# water_controller_1.net
KiCad netlist of a schematic drawn in Altium Designer
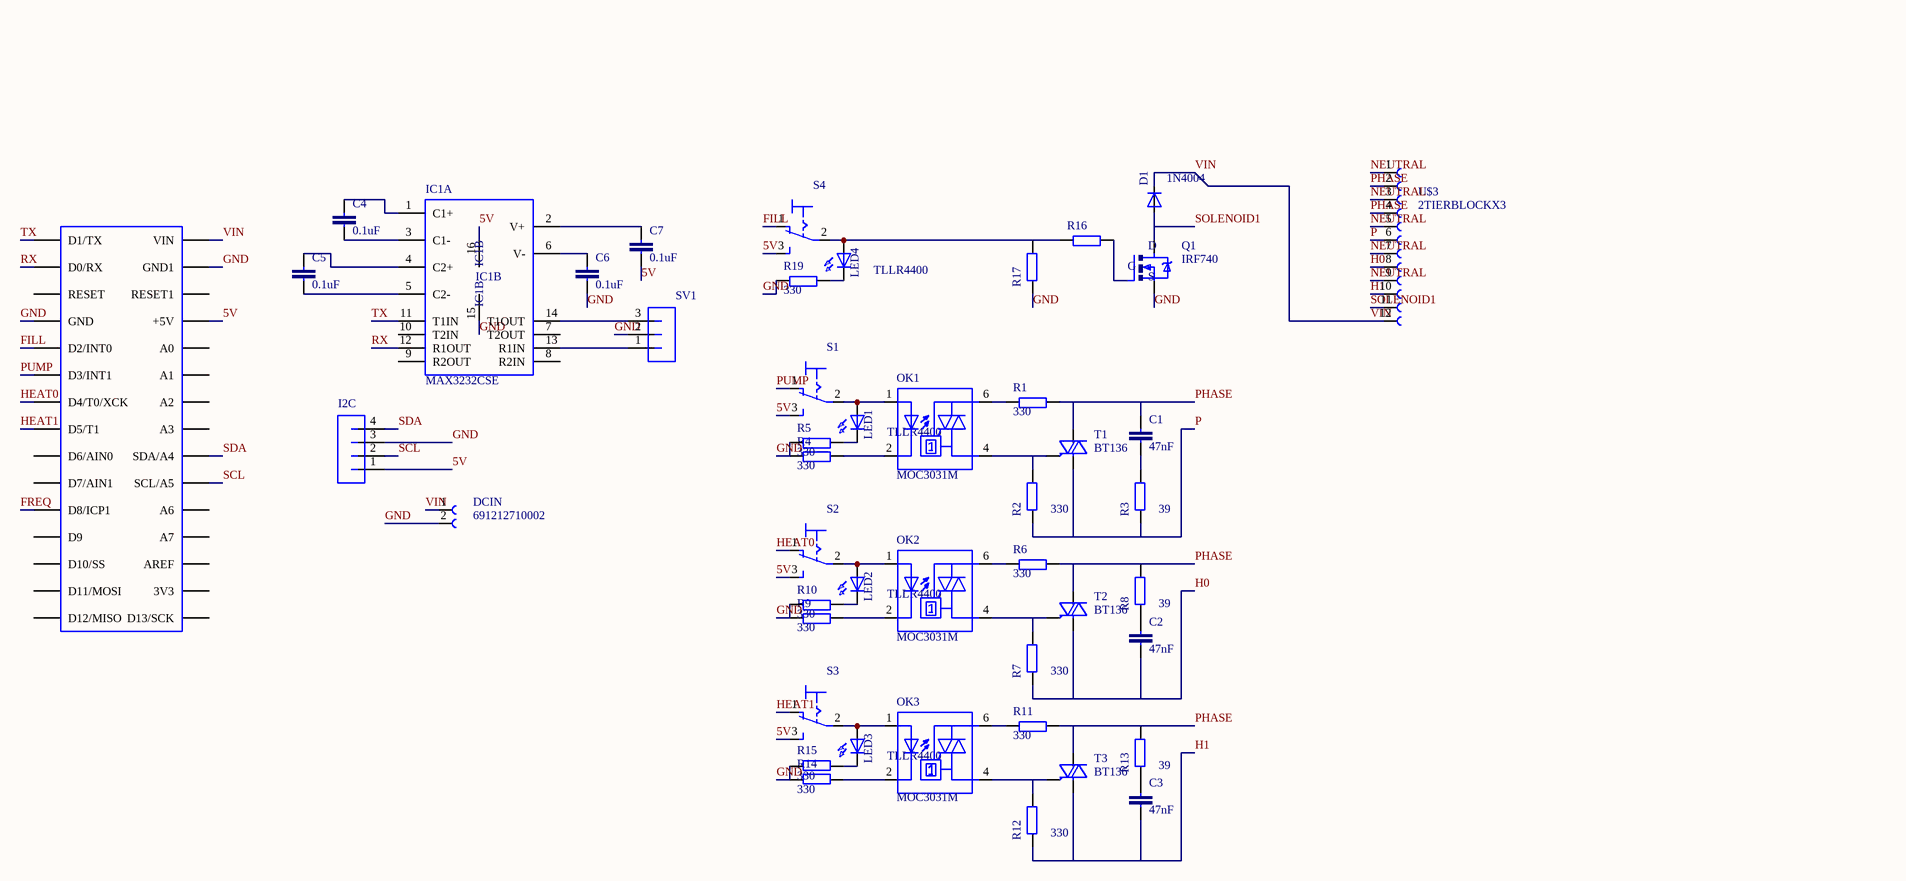
[diagram p0: water_controller_1.SchDoc]

(export (version "E")
  (design (tool "Eeschema 10.0.6"))
  (components
    (comp (ref "C1")
      (value "47nF")
      (footprint "C150-064X183")
      (libsource (lib "rcl") (part "C-EU150-064X183"))
    )
    (comp (ref "C2")
      (value "47nF")
      (footprint "C150-064X183")
      (libsource (lib "rcl") (part "C-EU150-064X183"))
    )
    (comp (ref "C3")
      (value "47nF")
      (footprint "C150-064X183")
      (libsource (lib "rcl") (part "C-EU150-064X183"))
    )
    (comp (ref "C4") (value "0.1uF") (footprint "C1210") (libsource (lib "rcl") (part "C-EUC1210")))
    (comp (ref "C5") (value "0.1uF") (footprint "C1210") (libsource (lib "rcl") (part "C-EUC1210")))
    (comp (ref "C6") (value "0.1uF") (footprint "C1210") (libsource (lib "rcl") (part "C-EUC1210")))
    (comp (ref "C7") (value "0.1uF") (footprint "C1210") (libsource (lib "rcl") (part "C-EUC1210")))
    (comp (ref "D1") (value "1N4004") (footprint "DO41-10") (libsource (lib "diode") (part "1N4004")))
    (comp (ref "DCIN")
      (value "691212710002")
      (footprint "691212710002")
      (libsource (lib "ZugbuegelsystemWR-TBL") (part "691212710002"))
    )
    (comp (ref "I2C") (value "~") (footprint "MA04-1") (libsource (lib "con-lstb") (part "MA04-1")))
    (comp (ref "IC1") (value "MAX3232CSE") (footprint "SO16") (libsource (lib "") (part "MAX3232CSE_1")))
    (comp (ref "LED1") (value "TLLR4400") (footprint "LED3MM") (libsource (lib "led") (part "TLLR4400")))
    (comp (ref "LED2") (value "TLLR4400") (footprint "LED3MM") (libsource (lib "led") (part "TLLR4400")))
    (comp (ref "LED3") (value "TLLR4400") (footprint "LED3MM") (libsource (lib "") (part "TLLR4400_1")))
    (comp (ref "LED4") (value "TLLR4400") (footprint "LED3MM") (libsource (lib "led") (part "TLLR4400")))
    (comp (ref "OK1")
      (value "MOC3031M")
      (footprint "DIL06")
      (libsource (lib "optocoupler") (part "MOC3031M"))
    )
    (comp (ref "OK2")
      (value "MOC3031M")
      (footprint "DIL06")
      (libsource (lib "optocoupler") (part "MOC3031M"))
    )
    (comp (ref "OK3")
      (value "MOC3031M")
      (footprint "DIL06")
      (libsource (lib "optocoupler") (part "MOC3031M"))
    )
    (comp (ref "Q1")
      (value "IRF740")
      (footprint "TO220BV")
      (libsource (lib "transistor-power") (part "IRF740"))
    )
    (comp (ref "R1") (value "330") (footprint "M1206") (libsource (lib "rcl") (part "R-EU_M1206")))
    (comp (ref "R2") (value "330") (footprint "M1206") (libsource (lib "") (part "R-EU_M1206_1")))
    (comp (ref "R3") (value "39") (footprint "M1206") (libsource (lib "") (part "R-EU_M1206_1")))
    (comp (ref "R4") (value "330") (footprint "R1206") (libsource (lib "rcl") (part "R-EU_R1206")))
    (comp (ref "R5") (value "330") (footprint "R1206") (libsource (lib "rcl") (part "R-EU_R1206")))
    (comp (ref "R6") (value "330") (footprint "M1206") (libsource (lib "rcl") (part "R-EU_M1206")))
    (comp (ref "R7") (value "330") (footprint "M1206") (libsource (lib "") (part "R-EU_M1206_1")))
    (comp (ref "R8") (value "39") (footprint "M1206") (libsource (lib "") (part "R-EU_M1206_1")))
    (comp (ref "R9") (value "330") (footprint "R1206") (libsource (lib "rcl") (part "R-EU_R1206")))
    (comp (ref "R10") (value "330") (footprint "R1206") (libsource (lib "rcl") (part "R-EU_R1206")))
    (comp (ref "R11") (value "330") (footprint "M1206") (libsource (lib "rcl") (part "R-EU_M1206")))
    (comp (ref "R12") (value "330") (footprint "M1206") (libsource (lib "") (part "R-EU_M1206_1")))
    (comp (ref "R13") (value "39") (footprint "M1206") (libsource (lib "") (part "R-EU_M1206_1")))
    (comp (ref "R14") (value "330") (footprint "R1206") (libsource (lib "") (part "R-EU_R1206_1")))
    (comp (ref "R15") (value "330") (footprint "R1206") (libsource (lib "") (part "R-EU_R1206_1")))
    (comp (ref "R16") (value "~") (footprint "M1206") (libsource (lib "rcl") (part "R-EU_M1206")))
    (comp (ref "R17") (value "~") (footprint "M1206") (libsource (lib "") (part "R-EU_M1206_1")))
    (comp (ref "R19") (value "330") (footprint "R1206") (libsource (lib "rcl") (part "R-EU_R1206")))
    (comp (ref "S1") (value "~") (footprint "M9040P") (libsource (lib "switch") (part "M9040P")))
    (comp (ref "S2") (value "~") (footprint "M9040P") (libsource (lib "switch") (part "M9040P")))
    (comp (ref "S3") (value "~") (footprint "M9040P") (libsource (lib "switch") (part "M9040P")))
    (comp (ref "S4") (value "~") (footprint "M9040P") (libsource (lib "switch") (part "M9040P")))
    (comp (ref "SV1") (value "~") (footprint "MA03-1") (libsource (lib "con-lstb") (part "MA03-1")))
    (comp (ref "T1") (value "BT136") (footprint "TO220AVH") (libsource (lib "jet-lib") (part "BT136")))
    (comp (ref "T2") (value "BT136") (footprint "TO220AVH") (libsource (lib "jet-lib") (part "BT136")))
    (comp (ref "T3") (value "BT136") (footprint "TO220AVH") (libsource (lib "jet-lib") (part "BT136")))
    (comp (ref "U$1") (value "~") (footprint "PDIP-32") (libsource (lib "jet-lib") (part "ARDUINONANO")))
    (comp (ref "U$3")
      (value "2TIERBLOCKX3")
      (footprint "2TIERX3")
      (libsource (lib "jet-lib") (part "2TIERBLOCKX3"))
    )
  )
  (nets
    (net (code "1") (name "/5V") (class "Default")
      (node (ref "C7") (pin "2") (pinfunction "2_2") (pintype "passive"))
      (node (ref "I2C") (pin "1") (pinfunction "1_1") (pintype "passive"))
      (node (ref "IC1") (pin "16") (pinfunction "VCC_16") (pintype "passive"))
      (node (ref "S1") (pin "3") (pinfunction "S_3") (pintype "passive"))
      (node (ref "S2") (pin "3") (pinfunction "S_3") (pintype "passive"))
      (node (ref "S3") (pin "3") (pinfunction "S_3") (pintype "passive"))
      (node (ref "S4") (pin "3") (pinfunction "S_3") (pintype "passive"))
      (node (ref "U$1") (pin "+5V") (pinfunction "+5V_+5V") (pintype "passive"))
    )
    (net (code "2") (name "/FILL") (class "Default")
      (node (ref "S4") (pin "1") (pinfunction "O_1") (pintype "passive"))
      (node (ref "U$1") (pin "D2") (pinfunction "D2/INT0_D2") (pintype "passive"))
    )
    (net (code "3") (name "/FREQ") (class "Default")
      (node (ref "U$1") (pin "D8") (pinfunction "D8/ICP1_D8") (pintype "passive"))
    )
    (net (code "4") (name "/GND") (class "Default")
      (node (ref "C6") (pin "2") (pinfunction "2_2") (pintype "passive"))
      (node (ref "DCIN") (pin "2") (pinfunction "2_2") (pintype "passive"))
      (node (ref "I2C") (pin "3") (pinfunction "3_3") (pintype "passive"))
      (node (ref "IC1") (pin "15") (pinfunction "GND_15") (pintype "passive"))
      (node (ref "Q1") (pin "S") (pinfunction "S_S") (pintype "passive"))
      (node (ref "R10") (pin "1") (pinfunction "1_1") (pintype "passive"))
      (node (ref "R14") (pin "1") (pinfunction "1_1") (pintype "passive"))
      (node (ref "R15") (pin "1") (pinfunction "1_1") (pintype "passive"))
      (node (ref "R17") (pin "1") (pinfunction "1_1") (pintype "passive"))
      (node (ref "R19") (pin "1") (pinfunction "1_1") (pintype "passive"))
      (node (ref "R4") (pin "1") (pinfunction "1_1") (pintype "passive"))
      (node (ref "R5") (pin "1") (pinfunction "1_1") (pintype "passive"))
      (node (ref "R9") (pin "1") (pinfunction "1_1") (pintype "passive"))
      (node (ref "SV1") (pin "2") (pinfunction "2_2") (pintype "passive"))
      (node (ref "U$1") (pin "GND") (pinfunction "GND_GND") (pintype "passive"))
      (node (ref "U$1") (pin "GND1") (pinfunction "GND1_GND1") (pintype "passive"))
    )
    (net (code "5") (name "/H0") (class "Default")
      (node (ref "C2") (pin "2") (pinfunction "2_2") (pintype "passive"))
      (node (ref "R7") (pin "1") (pinfunction "1_1") (pintype "passive"))
      (node (ref "T2") (pin "1") (pinfunction "T1_1") (pintype "passive"))
      (node (ref "U$3") (pin "8") (pinfunction "8_8") (pintype "passive"))
    )
    (net (code "6") (name "/H1") (class "Default")
      (node (ref "C3") (pin "2") (pinfunction "2_2") (pintype "passive"))
      (node (ref "R12") (pin "1") (pinfunction "1_1") (pintype "passive"))
      (node (ref "T3") (pin "1") (pinfunction "T1_1") (pintype "passive"))
      (node (ref "U$3") (pin "10") (pinfunction "10_10") (pintype "passive"))
    )
    (net (code "7") (name "/HEAT0") (class "Default")
      (node (ref "S2") (pin "1") (pinfunction "O_1") (pintype "passive"))
      (node (ref "U$1") (pin "D4") (pinfunction "D4/T0/XCK_D4") (pintype "passive"))
    )
    (net (code "8") (name "/HEAT1") (class "Default")
      (node (ref "S3") (pin "1") (pinfunction "O_1") (pintype "passive"))
      (node (ref "U$1") (pin "D5") (pinfunction "D5/T1_D5") (pintype "passive"))
    )
    (net (code "9") (name "/NEUTRAL") (class "Default")
      (node (ref "U$3") (pin "1") (pinfunction "1_1") (pintype "passive"))
      (node (ref "U$3") (pin "3") (pinfunction "3_3") (pintype "passive"))
      (node (ref "U$3") (pin "5") (pinfunction "5_5") (pintype "passive"))
      (node (ref "U$3") (pin "7") (pinfunction "7_7") (pintype "passive"))
      (node (ref "U$3") (pin "9") (pinfunction "9_9") (pintype "passive"))
    )
    (net (code "10") (name "/P") (class "Default")
      (node (ref "R2") (pin "1") (pinfunction "1_1") (pintype "passive"))
      (node (ref "R3") (pin "1") (pinfunction "1_1") (pintype "passive"))
      (node (ref "T1") (pin "1") (pinfunction "T1_1") (pintype "passive"))
      (node (ref "U$3") (pin "6") (pinfunction "6_6") (pintype "passive"))
    )
    (net (code "11") (name "/PHASE") (class "Default")
      (node (ref "C1") (pin "1") (pinfunction "1_1") (pintype "passive"))
      (node (ref "R1") (pin "2") (pinfunction "2_2") (pintype "passive"))
      (node (ref "R11") (pin "2") (pinfunction "2_2") (pintype "passive"))
      (node (ref "R13") (pin "2") (pinfunction "2_2") (pintype "passive"))
      (node (ref "R6") (pin "2") (pinfunction "2_2") (pintype "passive"))
      (node (ref "R8") (pin "2") (pinfunction "2_2") (pintype "passive"))
      (node (ref "T1") (pin "2") (pinfunction "T2_2") (pintype "passive"))
      (node (ref "T2") (pin "2") (pinfunction "T2_2") (pintype "passive"))
      (node (ref "T3") (pin "2") (pinfunction "T2_2") (pintype "passive"))
      (node (ref "U$3") (pin "2") (pinfunction "2_2") (pintype "passive"))
      (node (ref "U$3") (pin "4") (pinfunction "4_4") (pintype "passive"))
    )
    (net (code "12") (name "/PUMP") (class "Default")
      (node (ref "S1") (pin "1") (pinfunction "O_1") (pintype "passive"))
      (node (ref "U$1") (pin "D3") (pinfunction "D3/INT1_D3") (pintype "passive"))
    )
    (net (code "13") (name "/RX") (class "Default")
      (node (ref "IC1") (pin "12") (pinfunction "R1OUT_12") (pintype "passive"))
      (node (ref "U$1") (pin "D0/RX") (pinfunction "D0/RX_D0/RX") (pintype "passive"))
    )
    (net (code "14") (name "/SCL") (class "Default")
      (node (ref "I2C") (pin "2") (pinfunction "2_2") (pintype "passive"))
      (node (ref "U$1") (pin "A5") (pinfunction "SCL/A5_A5") (pintype "passive"))
    )
    (net (code "15") (name "/SDA") (class "Default")
      (node (ref "I2C") (pin "4") (pinfunction "4_4") (pintype "passive"))
      (node (ref "U$1") (pin "A4") (pinfunction "SDA/A4_A4") (pintype "passive"))
    )
    (net (code "16") (name "/SOLENOID1") (class "Default")
      (node (ref "D1") (pin "A") (pinfunction "A_A") (pintype "passive"))
      (node (ref "Q1") (pin "D") (pinfunction "D_D") (pintype "passive"))
      (node (ref "U$3") (pin "11") (pinfunction "11_11") (pintype "passive"))
    )
    (net (code "17") (name "/TX") (class "Default")
      (node (ref "IC1") (pin "11") (pinfunction "T1IN_11") (pintype "passive"))
      (node (ref "U$1") (pin "D1/TX") (pinfunction "D1/TX_D1/TX") (pintype "passive"))
    )
    (net (code "18") (name "/VIN") (class "Default")
      (node (ref "D1") (pin "C") (pinfunction "C_C") (pintype "passive"))
      (node (ref "DCIN") (pin "1") (pinfunction "1_1") (pintype "passive"))
      (node (ref "U$1") (pin "VIN") (pinfunction "VIN_VIN") (pintype "passive"))
      (node (ref "U$3") (pin "12") (pinfunction "12_12") (pintype "passive"))
    )
    (net (code "19") (name "Net-(C1-Pad2)") (class "Default")
      (node (ref "C1") (pin "2") (pinfunction "2_2") (pintype "passive"))
      (node (ref "R3") (pin "2") (pinfunction "2_2") (pintype "passive"))
    )
    (net (code "20") (name "Net-(C2-Pad1)") (class "Default")
      (node (ref "C2") (pin "1") (pinfunction "1_1") (pintype "passive"))
      (node (ref "R8") (pin "1") (pinfunction "1_1") (pintype "passive"))
    )
    (net (code "21") (name "Net-(C3-Pad1)") (class "Default")
      (node (ref "C3") (pin "1") (pinfunction "1_1") (pintype "passive"))
      (node (ref "R13") (pin "1") (pinfunction "1_1") (pintype "passive"))
    )
    (net (code "22") (name "Net-(IC1A-C1+)") (class "Default")
      (node (ref "C4") (pin "1") (pinfunction "1_1") (pintype "passive"))
      (node (ref "IC1") (pin "1") (pinfunction "C1+_1") (pintype "passive"))
    )
    (net (code "23") (name "Net-(IC1A-C1-)") (class "Default")
      (node (ref "C4") (pin "2") (pinfunction "2_2") (pintype "passive"))
      (node (ref "IC1") (pin "3") (pinfunction "C1-_3") (pintype "passive"))
    )
    (net (code "24") (name "Net-(IC1A-C2+)") (class "Default")
      (node (ref "C5") (pin "1") (pinfunction "1_1") (pintype "passive"))
      (node (ref "IC1") (pin "4") (pinfunction "C2+_4") (pintype "passive"))
    )
    (net (code "25") (name "Net-(IC1A-C2-)") (class "Default")
      (node (ref "C5") (pin "2") (pinfunction "2_2") (pintype "passive"))
      (node (ref "IC1") (pin "5") (pinfunction "C2-_5") (pintype "passive"))
    )
    (net (code "26") (name "Net-(IC1A-R1IN)") (class "Default")
      (node (ref "IC1") (pin "13") (pinfunction "R1IN_13") (pintype "passive"))
      (node (ref "SV1") (pin "1") (pinfunction "1_1") (pintype "passive"))
    )
    (net (code "27") (name "Net-(IC1A-T1OUT)") (class "Default")
      (node (ref "IC1") (pin "14") (pinfunction "T1OUT_14") (pintype "passive"))
      (node (ref "SV1") (pin "3") (pinfunction "3_3") (pintype "passive"))
    )
    (net (code "28") (name "Net-(IC1A-V+)") (class "Default")
      (node (ref "C7") (pin "1") (pinfunction "1_1") (pintype "passive"))
      (node (ref "IC1") (pin "2") (pinfunction "V+_2") (pintype "passive"))
    )
    (net (code "29") (name "Net-(IC1A-V-)") (class "Default")
      (node (ref "C6") (pin "1") (pinfunction "1_1") (pintype "passive"))
      (node (ref "IC1") (pin "6") (pinfunction "V-_6") (pintype "passive"))
    )
    (net (code "30") (name "Net-(LED1-C)") (class "Default")
      (node (ref "LED1") (pin "K") (pinfunction "C_K") (pintype "passive"))
      (node (ref "R5") (pin "2") (pinfunction "2_2") (pintype "passive"))
    )
    (net (code "31") (name "Net-(LED2-C)") (class "Default")
      (node (ref "LED2") (pin "K") (pinfunction "C_K") (pintype "passive"))
      (node (ref "R10") (pin "2") (pinfunction "2_2") (pintype "passive"))
    )
    (net (code "32") (name "Net-(LED3-C)") (class "Default")
      (node (ref "LED3") (pin "K") (pinfunction "C_K") (pintype "passive"))
      (node (ref "R15") (pin "2") (pinfunction "2_2") (pintype "passive"))
    )
    (net (code "33") (name "Net-(LED4-C)") (class "Default")
      (node (ref "LED4") (pin "K") (pinfunction "C_K") (pintype "passive"))
      (node (ref "R19") (pin "2") (pinfunction "2_2") (pintype "passive"))
    )
    (net (code "34") (name "Net-(OK1-A)") (class "Default")
      (node (ref "LED1") (pin "A") (pinfunction "A_A") (pintype "passive"))
      (node (ref "OK1") (pin "1") (pinfunction "A_1") (pintype "passive"))
      (node (ref "S1") (pin "2") (pinfunction "P_2") (pintype "passive"))
    )
    (net (code "35") (name "Net-(OK1-A1)") (class "Default")
      (node (ref "OK1") (pin "4") (pinfunction "A1_4") (pintype "passive"))
      (node (ref "R2") (pin "2") (pinfunction "2_2") (pintype "passive"))
      (node (ref "T1") (pin "3") (pinfunction "G_3") (pintype "passive"))
    )
    (net (code "36") (name "Net-(OK1-A2)") (class "Default")
      (node (ref "OK1") (pin "6") (pinfunction "A2_6") (pintype "passive"))
      (node (ref "R1") (pin "1") (pinfunction "1_1") (pintype "passive"))
    )
    (net (code "37") (name "Net-(OK1-C)") (class "Default")
      (node (ref "OK1") (pin "2") (pinfunction "C_2") (pintype "passive"))
      (node (ref "R4") (pin "2") (pinfunction "2_2") (pintype "passive"))
    )
    (net (code "38") (name "Net-(OK2-A)") (class "Default")
      (node (ref "LED2") (pin "A") (pinfunction "A_A") (pintype "passive"))
      (node (ref "OK2") (pin "1") (pinfunction "A_1") (pintype "passive"))
      (node (ref "S2") (pin "2") (pinfunction "P_2") (pintype "passive"))
    )
    (net (code "39") (name "Net-(OK2-A1)") (class "Default")
      (node (ref "OK2") (pin "4") (pinfunction "A1_4") (pintype "passive"))
      (node (ref "R7") (pin "2") (pinfunction "2_2") (pintype "passive"))
      (node (ref "T2") (pin "3") (pinfunction "G_3") (pintype "passive"))
    )
    (net (code "40") (name "Net-(OK2-A2)") (class "Default")
      (node (ref "OK2") (pin "6") (pinfunction "A2_6") (pintype "passive"))
      (node (ref "R6") (pin "1") (pinfunction "1_1") (pintype "passive"))
    )
    (net (code "41") (name "Net-(OK2-C)") (class "Default")
      (node (ref "OK2") (pin "2") (pinfunction "C_2") (pintype "passive"))
      (node (ref "R9") (pin "2") (pinfunction "2_2") (pintype "passive"))
    )
    (net (code "42") (name "Net-(OK3-A)") (class "Default")
      (node (ref "LED3") (pin "A") (pinfunction "A_A") (pintype "passive"))
      (node (ref "OK3") (pin "1") (pinfunction "A_1") (pintype "passive"))
      (node (ref "S3") (pin "2") (pinfunction "P_2") (pintype "passive"))
    )
    (net (code "43") (name "Net-(OK3-A1)") (class "Default")
      (node (ref "OK3") (pin "4") (pinfunction "A1_4") (pintype "passive"))
      (node (ref "R12") (pin "2") (pinfunction "2_2") (pintype "passive"))
      (node (ref "T3") (pin "3") (pinfunction "G_3") (pintype "passive"))
    )
    (net (code "44") (name "Net-(OK3-A2)") (class "Default")
      (node (ref "OK3") (pin "6") (pinfunction "A2_6") (pintype "passive"))
      (node (ref "R11") (pin "1") (pinfunction "1_1") (pintype "passive"))
    )
    (net (code "45") (name "Net-(OK3-C)") (class "Default")
      (node (ref "OK3") (pin "2") (pinfunction "C_2") (pintype "passive"))
      (node (ref "R14") (pin "2") (pinfunction "2_2") (pintype "passive"))
    )
    (net (code "46") (name "Net-(Q1-PadG)") (class "Default")
      (node (ref "Q1") (pin "G") (pinfunction "G_G") (pintype "passive"))
      (node (ref "R16") (pin "2") (pinfunction "2_2") (pintype "passive"))
    )
    (net (code "47") (name "Net-(S4-P)") (class "Default")
      (node (ref "LED4") (pin "A") (pinfunction "A_A") (pintype "passive"))
      (node (ref "R16") (pin "1") (pinfunction "1_1") (pintype "passive"))
      (node (ref "R17") (pin "2") (pinfunction "2_2") (pintype "passive"))
      (node (ref "S4") (pin "2") (pinfunction "P_2") (pintype "passive"))
    )
    (net (code "48") (name "unconnected-(IC1A-R2IN-Pad8)") (class "Default")
      (node (ref "IC1") (pin "8") (pinfunction "R2IN_8") (pintype "passive"))
    )
    (net (code "49") (name "unconnected-(IC1A-R2OUT-Pad9)") (class "Default")
      (node (ref "IC1") (pin "9") (pinfunction "R2OUT_9") (pintype "passive"))
    )
    (net (code "50") (name "unconnected-(IC1A-T2IN-Pad10)") (class "Default")
      (node (ref "IC1") (pin "10") (pinfunction "T2IN_10") (pintype "passive"))
    )
    (net (code "51") (name "unconnected-(IC1A-T2OUT-Pad7)") (class "Default")
      (node (ref "IC1") (pin "7") (pinfunction "T2OUT_7") (pintype "passive"))
    )
    (net (code "52") (name "unconnected-(U$1-D6{slash}AIN0-PadD6)") (class "Default")
      (node (ref "U$1") (pin "D6") (pinfunction "D6/AIN0_D6") (pintype "passive"))
    )
    (net (code "53") (name "unconnected-(U$1-D7{slash}AIN1-PadD7)") (class "Default")
      (node (ref "U$1") (pin "D7") (pinfunction "D7/AIN1_D7") (pintype "passive"))
    )
    (net (code "54") (name "unconnected-(U$1-D10{slash}SS-PadD10)") (class "Default")
      (node (ref "U$1") (pin "D10") (pinfunction "D10/SS_D10") (pintype "passive"))
    )
    (net (code "55") (name "unconnected-(U$1-D11{slash}MOSI-PadD11)") (class "Default")
      (node (ref "U$1") (pin "D11") (pinfunction "D11/MOSI_D11") (pintype "passive"))
    )
    (net (code "56") (name "unconnected-(U$1-D12{slash}MISO-PadD12)") (class "Default")
      (node (ref "U$1") (pin "D12") (pinfunction "D12/MISO_D12") (pintype "passive"))
    )
    (net (code "57") (name "unconnected-(U$1-D13{slash}SCK-PadD13)") (class "Default")
      (node (ref "U$1") (pin "D13") (pinfunction "D13/SCK_D13") (pintype "passive"))
    )
    (net (code "58") (name "unconnected-(U$1-Pad3V3)") (class "Default")
      (node (ref "U$1") (pin "3V3") (pinfunction "3V3_3V3") (pintype "passive"))
    )
    (net (code "59") (name "unconnected-(U$1-PadA0)") (class "Default")
      (node (ref "U$1") (pin "A0") (pinfunction "A0_A0") (pintype "passive"))
    )
    (net (code "60") (name "unconnected-(U$1-PadA1)") (class "Default")
      (node (ref "U$1") (pin "A1") (pinfunction "A1_A1") (pintype "passive"))
    )
    (net (code "61") (name "unconnected-(U$1-PadA2)") (class "Default")
      (node (ref "U$1") (pin "A2") (pinfunction "A2_A2") (pintype "passive"))
    )
    (net (code "62") (name "unconnected-(U$1-PadA3)") (class "Default")
      (node (ref "U$1") (pin "A3") (pinfunction "A3_A3") (pintype "passive"))
    )
    (net (code "63") (name "unconnected-(U$1-PadA6)") (class "Default")
      (node (ref "U$1") (pin "A6") (pinfunction "A6_A6") (pintype "passive"))
    )
    (net (code "64") (name "unconnected-(U$1-PadA7)") (class "Default")
      (node (ref "U$1") (pin "A7") (pinfunction "A7_A7") (pintype "passive"))
    )
    (net (code "65") (name "unconnected-(U$1-PadAREF)") (class "Default")
      (node (ref "U$1") (pin "AREF") (pinfunction "AREF_AREF") (pintype "passive"))
    )
    (net (code "66") (name "unconnected-(U$1-PadD9)") (class "Default")
      (node (ref "U$1") (pin "D9") (pinfunction "D9_D9") (pintype "passive"))
    )
    (net (code "67") (name "unconnected-(U$1-PadRESET)") (class "Default")
      (node (ref "U$1") (pin "RESET") (pinfunction "RESET_RESET") (pintype "passive"))
    )
    (net (code "68") (name "unconnected-(U$1-PadRESET1)") (class "Default")
      (node (ref "U$1") (pin "RESET1") (pinfunction "RESET1_RESET1") (pintype "passive"))
    )
  )
)
